# voice-rev_03.net
KiCad netlist of a schematic drawn in EAGLE
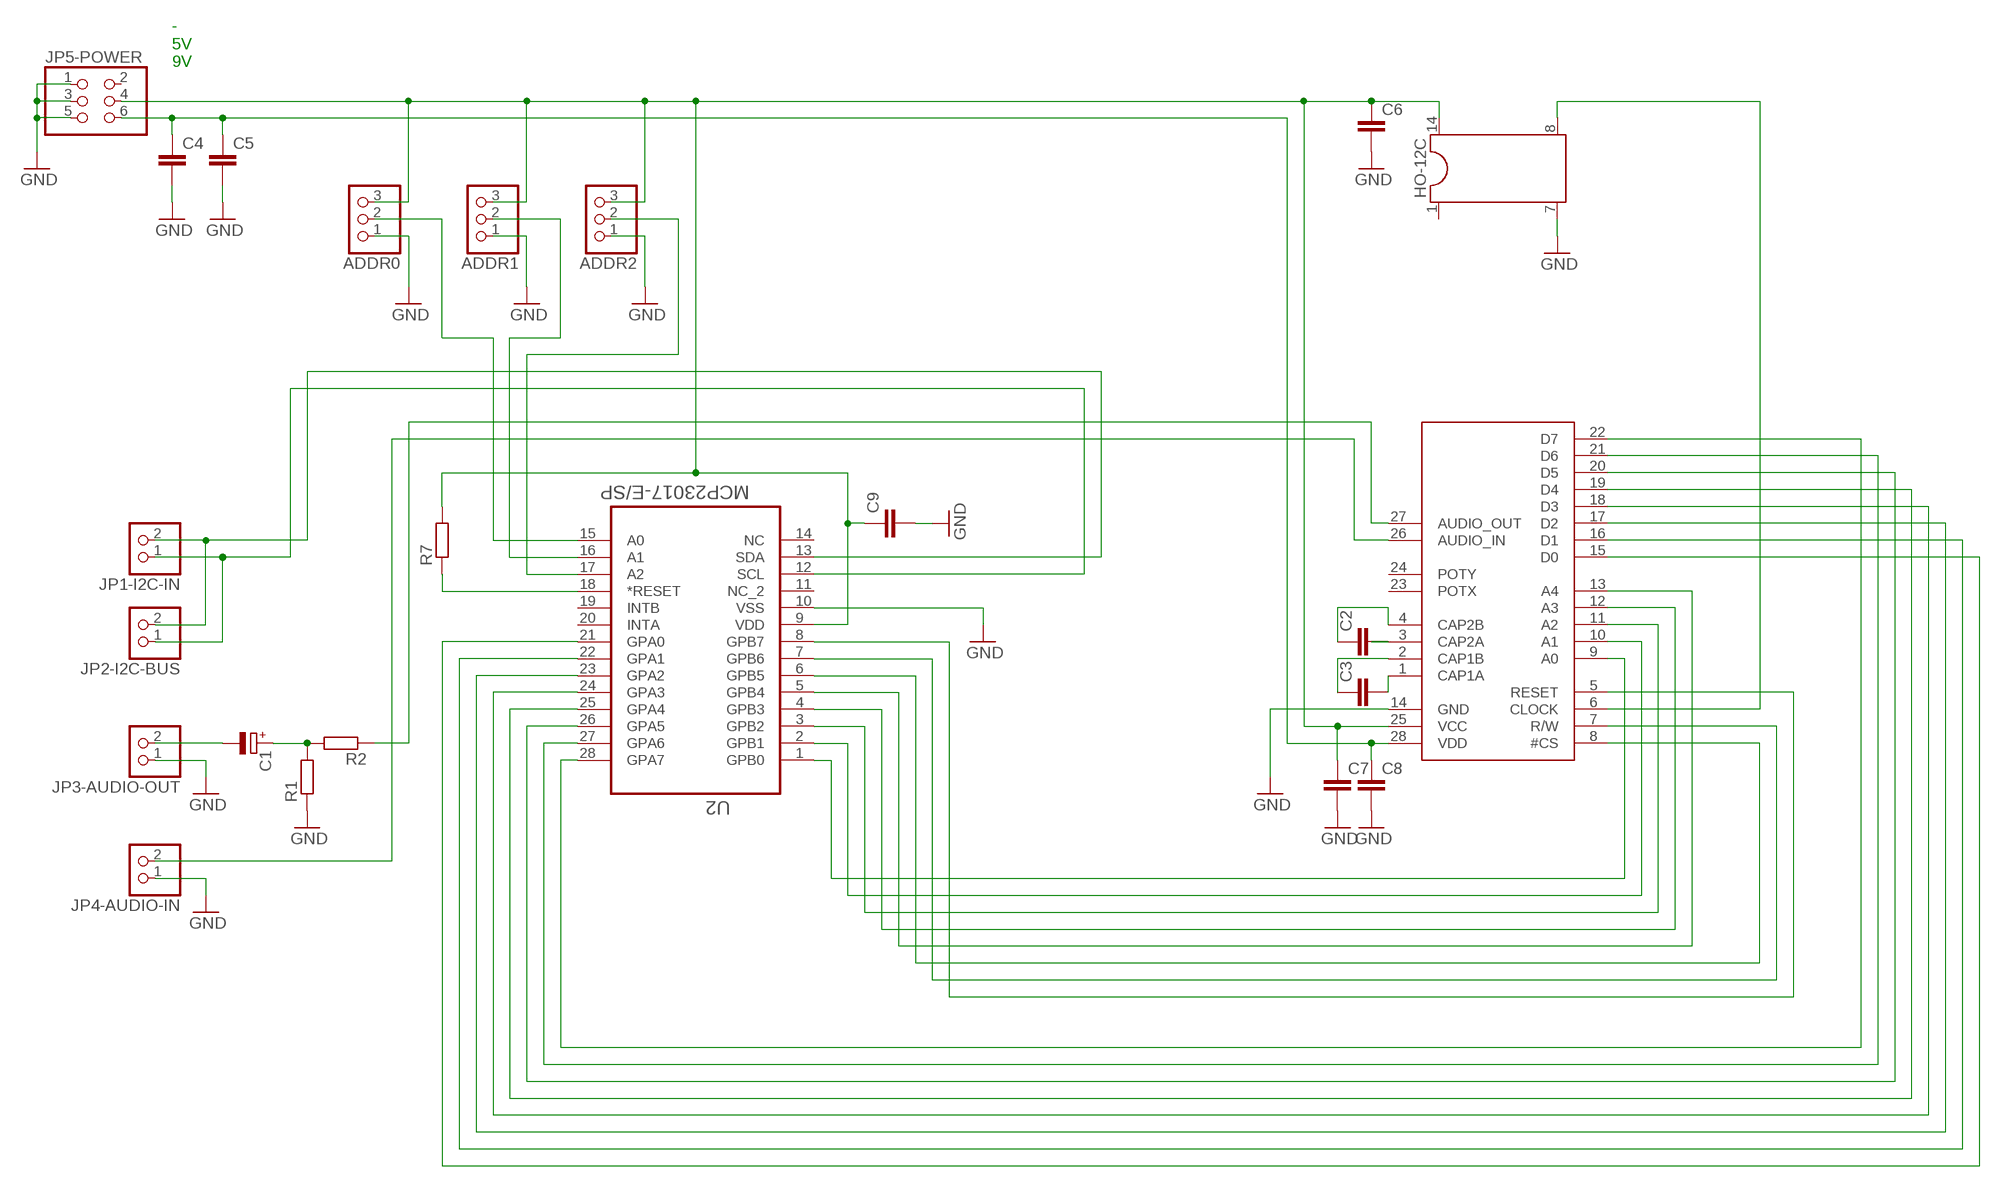
[diagram p0: schematic, sheet 1]

(export (version "E")
  (design (tool "Eeschema 10.0.6"))
  (components
    (comp (ref "ADDR0")
      (value "PINHD-1X3")
      (footprint "eagle-import:1X03")
      (libsource (lib "eagle-import") (part "PINHD-1X3"))
    )
    (comp (ref "ADDR1")
      (value "PINHD-1X3")
      (footprint "eagle-import:1X03")
      (libsource (lib "eagle-import") (part "PINHD-1X3"))
    )
    (comp (ref "ADDR2")
      (value "PINHD-1X3")
      (footprint "eagle-import:1X03")
      (libsource (lib "eagle-import") (part "PINHD-1X3"))
    )
    (comp (ref "C1")
      (value "CPOL-EUE2.5-5")
      (footprint "eagle-import:E2,5-5")
      (libsource (lib "eagle-import") (part "CPOL-EUE2.5-5"))
    )
    (comp (ref "C2")
      (value "C5/2.5")
      (footprint "eagle-import:C5B2.5")
      (libsource (lib "eagle-import") (part "C5/2.5"))
    )
    (comp (ref "C3")
      (value "C5/2.5")
      (footprint "eagle-import:C5B2.5")
      (libsource (lib "eagle-import") (part "C5/2.5"))
    )
    (comp (ref "C4")
      (value "C-EU050-024X044")
      (footprint "eagle-import:C050-024X044")
      (libsource (lib "eagle-import") (part "C-EU050-024X044"))
    )
    (comp (ref "C5")
      (value "C-EU050-024X044")
      (footprint "eagle-import:C050-024X044")
      (libsource (lib "eagle-import") (part "C-EU050-024X044"))
    )
    (comp (ref "C6")
      (value "C-EU050-024X044")
      (footprint "eagle-import:C050-024X044")
      (libsource (lib "eagle-import") (part "C-EU050-024X044"))
    )
    (comp (ref "C7")
      (value "C-EU050-024X044")
      (footprint "eagle-import:C050-024X044")
      (libsource (lib "eagle-import") (part "C-EU050-024X044"))
    )
    (comp (ref "C8")
      (value "C-EU050-024X044")
      (footprint "eagle-import:C050-024X044")
      (libsource (lib "eagle-import") (part "C-EU050-024X044"))
    )
    (comp (ref "C9")
      (value "C-EU050-024X044")
      (footprint "eagle-import:C050-024X044")
      (libsource (lib "eagle-import") (part "C-EU050-024X044"))
    )
    (comp (ref "HO-12C")
      (value "DIL14/4")
      (footprint "eagle-import:DIL14_4")
      (libsource (lib "eagle-import") (part "DIL14/4"))
    )
    (comp (ref "JP1-I2C-IN")
      (value "PINHD-1X2")
      (footprint "eagle-import:1X02")
      (libsource (lib "eagle-import") (part "PINHD-1X2"))
    )
    (comp (ref "JP2-I2C-BUS")
      (value "PINHD-1X2")
      (footprint "eagle-import:1X02")
      (libsource (lib "eagle-import") (part "PINHD-1X2"))
    )
    (comp (ref "JP3-AUDIO-OUT")
      (value "PINHD-1X2")
      (footprint "eagle-import:1X02")
      (libsource (lib "eagle-import") (part "PINHD-1X2"))
    )
    (comp (ref "JP4-AUDIO-IN")
      (value "PINHD-1X2")
      (footprint "eagle-import:1X02")
      (libsource (lib "eagle-import") (part "PINHD-1X2"))
    )
    (comp (ref "JP5-POWER")
      (value "PINHD-2X3")
      (footprint "eagle-import:2X03")
      (libsource (lib "eagle-import") (part "PINHD-2X3"))
    )
    (comp (ref "R1")
      (value "R-EU_0207/5V")
      (footprint "eagle-import:0207_5V")
      (libsource (lib "eagle-import") (part "R-EU_0207/5V"))
    )
    (comp (ref "R2")
      (value "R-EU_0207/5V")
      (footprint "eagle-import:0207_5V")
      (libsource (lib "eagle-import") (part "R-EU_0207/5V"))
    )
    (comp (ref "R7")
      (value "R-EU_0207/5V")
      (footprint "eagle-import:0207_5V")
      (libsource (lib "eagle-import") (part "R-EU_0207/5V"))
    )
    (comp (ref "U$1")
      (value "6581")
      (footprint "eagle-import:DIL28-6")
      (libsource (lib "eagle-import") (part "6581"))
    )
    (comp (ref "U2")
      (value "MCP23017-E/SP")
      (footprint "eagle-import:DIP254P762X406-28P")
      (libsource (lib "eagle-import") (part "MCP23017-E/SP"))
    )
  )
  (nets
    (net (code "1") (name "GND") (class "Default")
      (node (ref "ADDR0") (pin "1") (pinfunction "1_1") (pintype "passive"))
      (node (ref "ADDR1") (pin "1") (pinfunction "1_1") (pintype "passive"))
      (node (ref "ADDR2") (pin "1") (pinfunction "1_1") (pintype "passive"))
      (node (ref "C4") (pin "2") (pinfunction "2_2") (pintype "passive"))
      (node (ref "C5") (pin "2") (pinfunction "2_2") (pintype "passive"))
      (node (ref "C6") (pin "2") (pinfunction "2_2") (pintype "passive"))
      (node (ref "C7") (pin "2") (pinfunction "2_2") (pintype "passive"))
      (node (ref "C8") (pin "2") (pinfunction "2_2") (pintype "passive"))
      (node (ref "C9") (pin "2") (pinfunction "2_2") (pintype "passive"))
      (node (ref "HO-12C") (pin "7") (pinfunction "8_7") (pintype "passive"))
      (node (ref "JP3-AUDIO-OUT") (pin "1") (pinfunction "1_1") (pintype "passive"))
      (node (ref "JP4-AUDIO-IN") (pin "1") (pinfunction "1_1") (pintype "passive"))
      (node (ref "JP5-POWER") (pin "1") (pinfunction "1_1") (pintype "passive"))
      (node (ref "JP5-POWER") (pin "3") (pinfunction "3_3") (pintype "passive"))
      (node (ref "JP5-POWER") (pin "5") (pinfunction "5_5") (pintype "passive"))
      (node (ref "R1") (pin "1") (pinfunction "1_1") (pintype "passive"))
      (node (ref "U$1") (pin "14") (pinfunction "GND_14") (pintype "bidirectional"))
      (node (ref "U2") (pin "10") (pinfunction "VSS_10") (pintype "power_in"))
    )
    (net (code "2") (name "Net-(C1-Pad+)") (class "Default")
      (node (ref "C1") (pin "+") (pinfunction "+_+") (pintype "passive"))
      (node (ref "R1") (pin "2") (pinfunction "2_2") (pintype "passive"))
      (node (ref "R2") (pin "2") (pinfunction "2_2") (pintype "passive"))
    )
    (net (code "3") (name "Net-(C1-Pad-)") (class "Default")
      (node (ref "C1") (pin "-") (pinfunction "-_-") (pintype "passive"))
      (node (ref "JP3-AUDIO-OUT") (pin "2") (pinfunction "2_2") (pintype "passive"))
    )
    (net (code "4") (name "Net-(HO-12C-9)") (class "Default")
      (node (ref "HO-12C") (pin "8") (pinfunction "9_8") (pintype "passive"))
      (node (ref "U$1") (pin "6") (pinfunction "CLOCK_6") (pintype "bidirectional"))
    )
    (net (code "5") (name "Net-(HO-12C-16)") (class "Default")
      (node (ref "ADDR0") (pin "3") (pinfunction "3_3") (pintype "passive"))
      (node (ref "ADDR1") (pin "3") (pinfunction "3_3") (pintype "passive"))
      (node (ref "ADDR2") (pin "3") (pinfunction "3_3") (pintype "passive"))
      (node (ref "C6") (pin "1") (pinfunction "1_1") (pintype "passive"))
      (node (ref "C7") (pin "1") (pinfunction "1_1") (pintype "passive"))
      (node (ref "C9") (pin "1") (pinfunction "1_1") (pintype "passive"))
      (node (ref "HO-12C") (pin "14") (pinfunction "16_14") (pintype "passive"))
      (node (ref "JP5-POWER") (pin "4") (pinfunction "4_4") (pintype "passive"))
      (node (ref "R7") (pin "2") (pinfunction "2_2") (pintype "passive"))
      (node (ref "U$1") (pin "25") (pinfunction "VCC_25") (pintype "bidirectional"))
      (node (ref "U2") (pin "9") (pinfunction "VDD_9") (pintype "power_in"))
    )
    (net (code "6") (name "Net-(U$1-#CS)") (class "Default")
      (node (ref "U$1") (pin "8") (pinfunction "#CS_8") (pintype "bidirectional"))
      (node (ref "U2") (pin "6") (pinfunction "GPB5_6") (pintype "bidirectional"))
    )
    (net (code "7") (name "Net-(U$1-A0)") (class "Default")
      (node (ref "U$1") (pin "9") (pinfunction "A0_9") (pintype "bidirectional"))
      (node (ref "U2") (pin "1") (pinfunction "GPB0_1") (pintype "bidirectional"))
    )
    (net (code "8") (name "Net-(U$1-A1)") (class "Default")
      (node (ref "U$1") (pin "10") (pinfunction "A1_10") (pintype "bidirectional"))
      (node (ref "U2") (pin "2") (pinfunction "GPB1_2") (pintype "bidirectional"))
    )
    (net (code "9") (name "Net-(U$1-A2)") (class "Default")
      (node (ref "U$1") (pin "11") (pinfunction "A2_11") (pintype "bidirectional"))
      (node (ref "U2") (pin "3") (pinfunction "GPB2_3") (pintype "bidirectional"))
    )
    (net (code "10") (name "Net-(U$1-A3)") (class "Default")
      (node (ref "U$1") (pin "12") (pinfunction "A3_12") (pintype "bidirectional"))
      (node (ref "U2") (pin "4") (pinfunction "GPB3_4") (pintype "bidirectional"))
    )
    (net (code "11") (name "Net-(U$1-A4)") (class "Default")
      (node (ref "U$1") (pin "13") (pinfunction "A4_13") (pintype "bidirectional"))
      (node (ref "U2") (pin "5") (pinfunction "GPB4_5") (pintype "bidirectional"))
    )
    (net (code "12") (name "Net-(U$1-AUDIO_IN)") (class "Default")
      (node (ref "JP4-AUDIO-IN") (pin "2") (pinfunction "2_2") (pintype "passive"))
      (node (ref "U$1") (pin "26") (pinfunction "AUDIO_IN_26") (pintype "bidirectional"))
    )
    (net (code "13") (name "Net-(U$1-AUDIO_OUT)") (class "Default")
      (node (ref "R2") (pin "1") (pinfunction "1_1") (pintype "passive"))
      (node (ref "U$1") (pin "27") (pinfunction "AUDIO_OUT_27") (pintype "bidirectional"))
    )
    (net (code "14") (name "Net-(U$1-CAP1A)") (class "Default")
      (node (ref "C3") (pin "2") (pinfunction "2_2") (pintype "passive"))
      (node (ref "U$1") (pin "1") (pinfunction "CAP1A_1") (pintype "bidirectional"))
    )
    (net (code "15") (name "Net-(U$1-CAP1B)") (class "Default")
      (node (ref "C3") (pin "1") (pinfunction "1_1") (pintype "passive"))
      (node (ref "U$1") (pin "2") (pinfunction "CAP1B_2") (pintype "bidirectional"))
    )
    (net (code "16") (name "Net-(U$1-CAP2A)") (class "Default")
      (node (ref "C2") (pin "2") (pinfunction "2_2") (pintype "passive"))
      (node (ref "U$1") (pin "3") (pinfunction "CAP2A_3") (pintype "bidirectional"))
    )
    (net (code "17") (name "Net-(U$1-CAP2B)") (class "Default")
      (node (ref "C2") (pin "1") (pinfunction "1_1") (pintype "passive"))
      (node (ref "U$1") (pin "4") (pinfunction "CAP2B_4") (pintype "bidirectional"))
    )
    (net (code "18") (name "Net-(U$1-D0)") (class "Default")
      (node (ref "U$1") (pin "15") (pinfunction "D0_15") (pintype "bidirectional"))
      (node (ref "U2") (pin "21") (pinfunction "GPA0_21") (pintype "bidirectional"))
    )
    (net (code "19") (name "Net-(U$1-D1)") (class "Default")
      (node (ref "U$1") (pin "16") (pinfunction "D1_16") (pintype "bidirectional"))
      (node (ref "U2") (pin "22") (pinfunction "GPA1_22") (pintype "bidirectional"))
    )
    (net (code "20") (name "Net-(U$1-D2)") (class "Default")
      (node (ref "U$1") (pin "17") (pinfunction "D2_17") (pintype "bidirectional"))
      (node (ref "U2") (pin "23") (pinfunction "GPA2_23") (pintype "bidirectional"))
    )
    (net (code "21") (name "Net-(U$1-D3)") (class "Default")
      (node (ref "U$1") (pin "18") (pinfunction "D3_18") (pintype "bidirectional"))
      (node (ref "U2") (pin "24") (pinfunction "GPA3_24") (pintype "bidirectional"))
    )
    (net (code "22") (name "Net-(U$1-D4)") (class "Default")
      (node (ref "U$1") (pin "19") (pinfunction "D4_19") (pintype "bidirectional"))
      (node (ref "U2") (pin "25") (pinfunction "GPA4_25") (pintype "bidirectional"))
    )
    (net (code "23") (name "Net-(U$1-D5)") (class "Default")
      (node (ref "U$1") (pin "20") (pinfunction "D5_20") (pintype "bidirectional"))
      (node (ref "U2") (pin "26") (pinfunction "GPA5_26") (pintype "bidirectional"))
    )
    (net (code "24") (name "Net-(U$1-D6)") (class "Default")
      (node (ref "U$1") (pin "21") (pinfunction "D6_21") (pintype "bidirectional"))
      (node (ref "U2") (pin "27") (pinfunction "GPA6_27") (pintype "bidirectional"))
    )
    (net (code "25") (name "Net-(U$1-D7)") (class "Default")
      (node (ref "U$1") (pin "22") (pinfunction "D7_22") (pintype "bidirectional"))
      (node (ref "U2") (pin "28") (pinfunction "GPA7_28") (pintype "bidirectional"))
    )
    (net (code "26") (name "Net-(U$1-RESET)") (class "Default")
      (node (ref "U$1") (pin "5") (pinfunction "RESET_5") (pintype "bidirectional"))
      (node (ref "U2") (pin "8") (pinfunction "GPB7_8") (pintype "bidirectional"))
    )
    (net (code "27") (name "Net-(U$1-R{slash}W)") (class "Default")
      (node (ref "U$1") (pin "7") (pinfunction "R/W_7") (pintype "bidirectional"))
      (node (ref "U2") (pin "7") (pinfunction "GPB6_7") (pintype "bidirectional"))
    )
    (net (code "28") (name "Net-(U$1-VDD)") (class "Default")
      (node (ref "C4") (pin "1") (pinfunction "1_1") (pintype "passive"))
      (node (ref "C5") (pin "1") (pinfunction "1_1") (pintype "passive"))
      (node (ref "C8") (pin "1") (pinfunction "1_1") (pintype "passive"))
      (node (ref "JP5-POWER") (pin "6") (pinfunction "6_6") (pintype "passive"))
      (node (ref "U$1") (pin "28") (pinfunction "VDD_28") (pintype "bidirectional"))
    )
    (net (code "29") (name "Net-(U2-*RESET)") (class "Default")
      (node (ref "R7") (pin "1") (pinfunction "1_1") (pintype "passive"))
      (node (ref "U2") (pin "18") (pinfunction "*RESET_18") (pintype "output"))
    )
    (net (code "30") (name "Net-(U2-A0)") (class "Default")
      (node (ref "ADDR0") (pin "2") (pinfunction "2_2") (pintype "passive"))
      (node (ref "U2") (pin "15") (pinfunction "A0_15") (pintype "input"))
    )
    (net (code "31") (name "Net-(U2-A1)") (class "Default")
      (node (ref "ADDR1") (pin "2") (pinfunction "2_2") (pintype "passive"))
      (node (ref "U2") (pin "16") (pinfunction "A1_16") (pintype "input"))
    )
    (net (code "32") (name "Net-(U2-A2)") (class "Default")
      (node (ref "ADDR2") (pin "2") (pinfunction "2_2") (pintype "passive"))
      (node (ref "U2") (pin "17") (pinfunction "A2_17") (pintype "input"))
    )
    (net (code "33") (name "Net-(U2-SCL)") (class "Default")
      (node (ref "JP1-I2C-IN") (pin "1") (pinfunction "1_1") (pintype "passive"))
      (node (ref "JP2-I2C-BUS") (pin "1") (pinfunction "1_1") (pintype "passive"))
      (node (ref "U2") (pin "12") (pinfunction "SCL_12") (pintype "input"))
    )
    (net (code "34") (name "Net-(U2-SDA)") (class "Default")
      (node (ref "JP1-I2C-IN") (pin "2") (pinfunction "2_2") (pintype "passive"))
      (node (ref "JP2-I2C-BUS") (pin "2") (pinfunction "2_2") (pintype "passive"))
      (node (ref "U2") (pin "13") (pinfunction "SDA_13") (pintype "bidirectional"))
    )
    (net (code "35") (name "unconnected-(HO-12C-Pad1)") (class "Default")
      (node (ref "HO-12C") (pin "1") (pinfunction "1_1") (pintype "passive"))
    )
    (net (code "36") (name "unconnected-(JP5-POWER-Pad2)") (class "Default")
      (node (ref "JP5-POWER") (pin "2") (pinfunction "2_2") (pintype "passive"))
    )
    (net (code "37") (name "unconnected-(U$1-POTX-Pad23)") (class "Default")
      (node (ref "U$1") (pin "23") (pinfunction "POTX_23") (pintype "bidirectional"))
    )
    (net (code "38") (name "unconnected-(U$1-POTY-Pad24)") (class "Default")
      (node (ref "U$1") (pin "24") (pinfunction "POTY_24") (pintype "bidirectional"))
    )
    (net (code "39") (name "unconnected-(U2-INTA-Pad20)") (class "Default")
      (node (ref "U2") (pin "20") (pinfunction "INTA_20") (pintype "output"))
    )
    (net (code "40") (name "unconnected-(U2-INTB-Pad19)") (class "Default")
      (node (ref "U2") (pin "19") (pinfunction "INTB_19") (pintype "output"))
    )
    (net (code "41") (name "unconnected-(U2-NC-Pad14)") (class "Default")
      (node (ref "U2") (pin "14") (pinfunction "NC_14") (pintype "no_connect"))
    )
    (net (code "42") (name "unconnected-(U2-NC_2-Pad11)") (class "Default")
      (node (ref "U2") (pin "11") (pinfunction "NC_2_11") (pintype "no_connect"))
    )
  )
)
